# PowerAssembly.net
KiCad netlist of a schematic drawn in Altium Designer
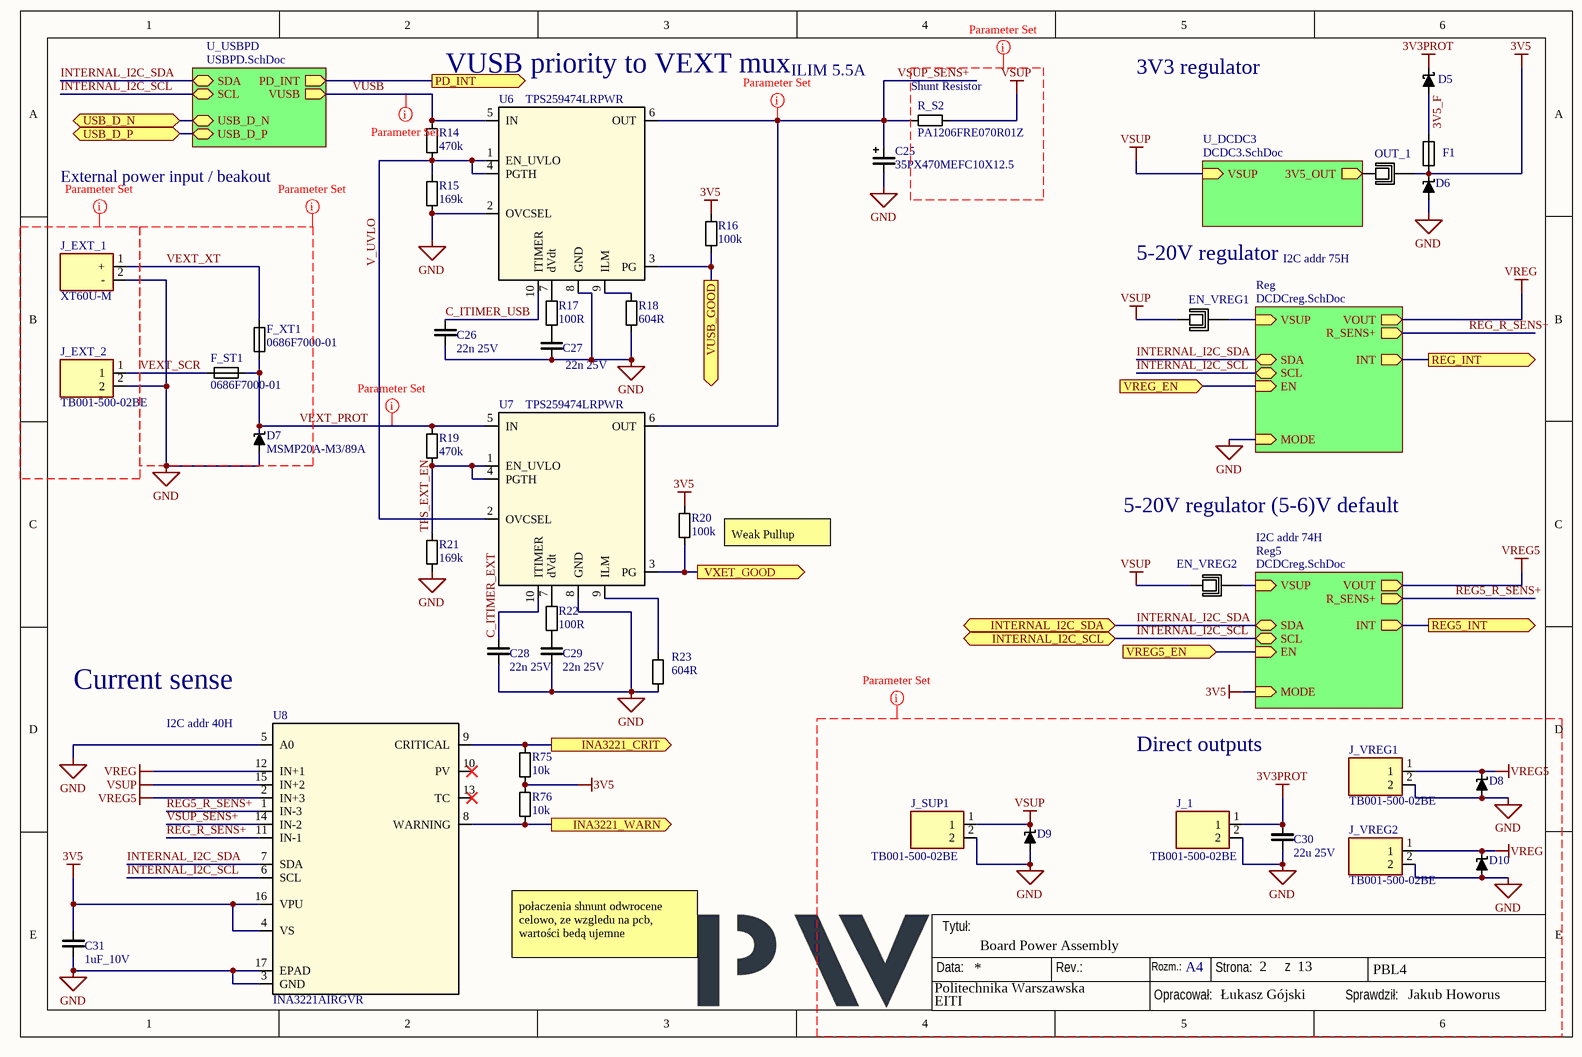
[diagram p0: PowerAssembly.SchDoc]

(export (version "E")
  (design (tool "Eeschema 10.0.6"))
  (components
    (comp (ref "C25")
      (value "35PX470MEFC10X12.5")
      (footprint "CAP_PKPZ_10X12P5_LOW_RUB")
      (description "470 µF 35 V Aluminum Electrolytic Capacitors Radial, Can 2000 Hrs @ 105°C")
      (fields (field (name "VOLTAGE") "35V") (field (name "TOLERANCE") "20%"))
      (libsource (lib "Common") (part "C_Pol_470uF_35V"))
    )
    (comp (ref "C26")
      (value "22n 25V")
      (footprint "C_0603")
      (description "Ceramic capacitor")
      (fields (field (name "VOLTAGE") "25V") (field (name "TOLERANCE") "10%"))
      (libsource (lib "Common") (part "C_22nF_25V"))
    )
    (comp (ref "C27")
      (value "22n 25V")
      (footprint "C_0603")
      (description "Ceramic capacitor")
      (fields (field (name "VOLTAGE") "25V") (field (name "TOLERANCE") "10%"))
      (libsource (lib "Common") (part "C_22nF_25V"))
    )
    (comp (ref "C28")
      (value "22n 25V")
      (footprint "C_0603")
      (description "Ceramic capacitor")
      (fields (field (name "VOLTAGE") "25V") (field (name "TOLERANCE") "10%"))
      (libsource (lib "Common") (part "C_22nF_25V"))
    )
    (comp (ref "C29")
      (value "22n 25V")
      (footprint "C_0603")
      (description "Ceramic capacitor")
      (fields (field (name "VOLTAGE") "25V") (field (name "TOLERANCE") "10%"))
      (libsource (lib "Common") (part "C_22nF_25V"))
    )
    (comp (ref "C30")
      (value "22u 25V")
      (footprint "C_1206")
      (description "Ceramic capacitor")
      (fields (field (name "VOLTAGE") "25V") (field (name "TOLERANCE") "20%"))
      (libsource (lib "Common") (part "C_22uF_25V"))
    )
    (comp (ref "C31")
      (value "1uF_10V")
      (footprint "C_0603")
      (description "Ceramic capacitor")
      (fields (field (name "VOLTAGE") "10V") (field (name "TOLERANCE") "10%"))
      (libsource (lib "Common") (part "C_1uF_10V"))
    )
    (comp (ref "D5")
      (value "SL12-E3/61T")
      (footprint "DIONM5127X229N")
      (description "Schottky Diode 1500mA 30V reverse")
      (libsource (lib "Common") (part "D schottky 1.5A"))
    )
    (comp (ref "D6")
      (value "MSMP20A-M3/89A")
      (footprint "CR_0A-M389A_VIS")
      (description "22V Breakdown MSMP20A-M3/89A")
      (libsource (lib "Common") (part "TVS_22V"))
    )
    (comp (ref "D7")
      (value "MSMP20A-M3/89A")
      (footprint "CR_0A-M389A_VIS")
      (description "22V Breakdown MSMP20A-M3/89A")
      (libsource (lib "Common") (part "TVS_22V"))
    )
    (comp (ref "D8")
      (value "MSMP20A-M3/89A")
      (footprint "CR_0A-M389A_VIS")
      (description "22V Breakdown MSMP20A-M3/89A")
      (libsource (lib "Common") (part "TVS_22V"))
    )
    (comp (ref "D9")
      (value "MSMP20A-M3/89A")
      (footprint "CR_0A-M389A_VIS")
      (description "22V Breakdown MSMP20A-M3/89A")
      (libsource (lib "Common") (part "TVS_22V"))
    )
    (comp (ref "D10")
      (value "MSMP20A-M3/89A")
      (footprint "CR_0A-M389A_VIS")
      (description "22V Breakdown MSMP20A-M3/89A")
      (libsource (lib "Common") (part "TVS_22V"))
    )
    (comp (ref "EN_VREG1")
      (value "JUMPER")
      (footprint "Jumper")
      (description "Jumper on traces")
      (libsource (lib "Common") (part "Jumper x2"))
    )
    (comp (ref "EN_VREG2")
      (value "JUMPER")
      (footprint "Jumper")
      (description "Jumper on traces")
      (libsource (lib "Common") (part "Jumper x2"))
    )
    (comp (ref "F1")
      (value "SD110-08")
      (footprint "1812")
      (description "FUSE PTC 1.1A 8VDC 2.2A TRIP")
      (libsource (lib "PowerLib") (part "PTC 1.1A FUSE"))
    )
    (comp (ref "F_ST1")
      (value "0686F7000-01")
      (footprint "0603_FUSE")
      (description "7A fuse 0603 package")
      (fields (field (name "MANUFACTURER") "Bel fuse Inc."))
      (libsource (lib "PowerLib") (part "F_7A"))
    )
    (comp (ref "F_XT1")
      (value "0686F7000-01")
      (footprint "0603_FUSE")
      (description "7A fuse 0603 package")
      (fields (field (name "MANUFACTURER") "Bel fuse Inc."))
      (libsource (lib "PowerLib") (part "F_7A"))
    )
    (comp (ref "J_1")
      (value "TB001-500-02BE")
      (footprint "TB00150002BE")
      (description "Screw terminal x2 5mm spacing")
      (fields (field (name "MANUFACTURER") "Same Sky"))
      (libsource (lib "Common") (part "Screw Terminal x2 5mm"))
    )
    (comp (ref "J_EXT_1")
      (value "XT60U-M")
      (footprint "XT60U-M")
      (description "XT60 male connector, ewentualnie dostępny w zasobach prywatnych (5szt)")
      (fields (field (name "MANUFACTURER") "AMASS"))
      (libsource (lib "PowerLib") (part "XT60"))
    )
    (comp (ref "J_EXT_2")
      (value "TB001-500-02BE")
      (footprint "TB00150002BE")
      (description "Screw terminal x2 5mm spacing")
      (fields (field (name "MANUFACTURER") "Same Sky"))
      (libsource (lib "Common") (part "Screw Terminal x2 5mm"))
    )
    (comp (ref "J_SUP1")
      (value "TB001-500-02BE")
      (footprint "TB00150002BE")
      (description "Screw terminal x2 5mm spacing")
      (fields (field (name "MANUFACTURER") "Same Sky"))
      (libsource (lib "Common") (part "Screw Terminal x2 5mm"))
    )
    (comp (ref "J_VREG1")
      (value "TB001-500-02BE")
      (footprint "TB00150002BE")
      (description "Screw terminal x2 5mm spacing")
      (fields (field (name "MANUFACTURER") "Same Sky"))
      (libsource (lib "Common") (part "Screw Terminal x2 5mm"))
    )
    (comp (ref "J_VREG2")
      (value "TB001-500-02BE")
      (footprint "TB00150002BE")
      (description "Screw terminal x2 5mm spacing")
      (fields (field (name "MANUFACTURER") "Same Sky"))
      (libsource (lib "Common") (part "Screw Terminal x2 5mm"))
    )
    (comp (ref "OUT_1")
      (value "JUMPER")
      (footprint "Jumper")
      (description "Jumper on traces")
      (libsource (lib "Common") (part "Jumper x2"))
    )
    (comp (ref "R14")
      (value "470k")
      (footprint "R_0603")
      (description "Resistor")
      (fields (field (name "TOLERANCE") "1%") (field (name "POWER") "100mW"))
      (libsource (lib "Common") (part "R_470k"))
    )
    (comp (ref "R15")
      (value "169k")
      (footprint "R_0603")
      (description "Resistor")
      (fields (field (name "TOLERANCE") "1%") (field (name "POWER") "100mW"))
      (libsource (lib "Common") (part "R_169k"))
    )
    (comp (ref "R16")
      (value "100k")
      (footprint "R_0603")
      (description "Resistor")
      (fields (field (name "TOLERANCE") "1%") (field (name "POWER") "100mW"))
      (libsource (lib "Common") (part "R_100k"))
    )
    (comp (ref "R17")
      (value "100R")
      (footprint "R_0603")
      (description "Resistor")
      (fields (field (name "TOLERANCE") "1%") (field (name "POWER") "100mW"))
      (libsource (lib "Common") (part "R_100R"))
    )
    (comp (ref "R18")
      (value "604R")
      (footprint "R_0603")
      (description "Resistor")
      (fields (field (name "TOLERANCE") "1%") (field (name "POWER") "100mW"))
      (libsource (lib "Common") (part "R_604R"))
    )
    (comp (ref "R19")
      (value "470k")
      (footprint "R_0603")
      (description "Resistor")
      (fields (field (name "TOLERANCE") "1%") (field (name "POWER") "100mW"))
      (libsource (lib "Common") (part "R_470k"))
    )
    (comp (ref "R20")
      (value "100k")
      (footprint "R_0603")
      (description "Resistor")
      (fields (field (name "TOLERANCE") "1%") (field (name "POWER") "100mW"))
      (libsource (lib "Common") (part "R_100k"))
    )
    (comp (ref "R21")
      (value "169k")
      (footprint "R_0603")
      (description "Resistor")
      (fields (field (name "TOLERANCE") "1%") (field (name "POWER") "100mW"))
      (libsource (lib "Common") (part "R_169k"))
    )
    (comp (ref "R22")
      (value "100R")
      (footprint "R_0603")
      (description "Resistor")
      (fields (field (name "TOLERANCE") "1%") (field (name "POWER") "100mW"))
      (libsource (lib "Common") (part "R_100R"))
    )
    (comp (ref "R23")
      (value "604R")
      (footprint "R_0603")
      (description "Resistor")
      (fields (field (name "TOLERANCE") "1%") (field (name "POWER") "100mW"))
      (libsource (lib "Common") (part "R_604R"))
    )
    (comp (ref "R75")
      (value "10k")
      (footprint "R_0603")
      (description "Resistor")
      (fields (field (name "TOLERANCE") "1%") (field (name "POWER") "100mW"))
      (libsource (lib "Common") (part "R_10k"))
    )
    (comp (ref "R76")
      (value "10k")
      (footprint "R_0603")
      (description "Resistor")
      (fields (field (name "TOLERANCE") "1%") (field (name "POWER") "100mW"))
      (libsource (lib "Common") (part "R_10k"))
    )
    (comp (ref "R_S2")
      (value "PA1206FRE070R01Z")
      (footprint "R_1206")
      (description "Shunt Resistor 10 mR, 1206, 250mW")
      (fields (field (name "TOLERANCE") "1%") (field (name "POWER") "250mW"))
      (libsource (lib "PowerLib") (part "R_10mR"))
    )
    (comp (ref "U6")
      (value "TPS259474LRPWR")
      (footprint "RPW0010A-MFG")
      (description "2.7-V to 23-V, 5.5-A eFuse with integrated reverse polarity protection 10-VQFN-HR")
      (fields (field (name "MANUFACTURER") "Texas Instruments"))
      (libsource (lib "PowerLib") (part "TPS259474LRPWR"))
    )
    (comp (ref "U7")
      (value "TPS259474LRPWR")
      (footprint "RPW0010A-MFG")
      (description "2.7-V to 23-V, 5.5-A eFuse with integrated reverse polarity protection 10-VQFN-HR")
      (fields (field (name "MANUFACTURER") "Texas Instruments"))
      (libsource (lib "PowerLib") (part "TPS259474LRPWR"))
    )
    (comp (ref "U8")
      (value "INA3221AIRGVR")
      (footprint "RGV16_2P16X2P16")
      (description "26V, triple channel, 13-bit, i2c output current/voltage monitor w/alerts 16-VQFN")
      (fields (field (name "MANUFACTURER") "Texas Instruments"))
      (libsource (lib "PowerLib") (part "INA3221AIRGVR"))
    )
  )
  (nets
    (net (code "1") (name "/3V5_F") (class "Default")
      (node (ref "D5") (pin "A") (pinfunction "A_A") (pintype "passive"))
      (node (ref "F1") (pin "1") (pinfunction "1_1") (pintype "passive"))
    )
    (net (code "2") (name "/3V5_OUT") (class "Default")
      (node (ref "OUT_1") (pin "1") (pinfunction "1_1") (pintype "passive"))
    )
    (net (code "3") (name "/C_ITIMER_EXT") (class "Default")
      (node (ref "C28") (pin "2") (pinfunction "2_2") (pintype "passive"))
      (node (ref "U7") (pin "10") (pinfunction "ITIMER_10") (pintype "passive"))
    )
    (net (code "4") (name "/C_ITIMER_USB") (class "Default")
      (node (ref "C26") (pin "2") (pinfunction "2_2") (pintype "passive"))
      (node (ref "U6") (pin "10") (pinfunction "ITIMER_10") (pintype "passive"))
    )
    (net (code "5") (name "/INA3221_CRIT") (class "Default")
      (node (ref "R75") (pin "2") (pinfunction "2_2") (pintype "passive"))
      (node (ref "U8") (pin "9") (pinfunction "CRITICAL_9") (pintype "passive"))
    )
    (net (code "6") (name "/INA3221_WARN") (class "Default")
      (node (ref "R76") (pin "1") (pinfunction "1_1") (pintype "passive"))
      (node (ref "U8") (pin "8") (pinfunction "WARNING_8") (pintype "passive"))
    )
    (net (code "7") (name "/INTERNAL_I2C_SCL") (class "Default")
      (node (ref "U8") (pin "6") (pinfunction "SCL_6") (pintype "passive"))
    )
    (net (code "8") (name "/INTERNAL_I2C_SDA") (class "Default")
      (node (ref "U8") (pin "7") (pinfunction "SDA_7") (pintype "passive"))
    )
    (net (code "11") (name "/REG5_R_SENS+") (class "Default")
      (node (ref "U8") (pin "1") (pinfunction "IN-3_1") (pintype "passive"))
    )
    (net (code "13") (name "/REG_R_SENS+") (class "Default")
      (node (ref "U8") (pin "11") (pinfunction "IN-1_11") (pintype "passive"))
    )
    (net (code "14") (name "/TPS_EXT_EN") (class "Default")
      (node (ref "R19") (pin "1") (pinfunction "1_1") (pintype "passive"))
      (node (ref "R21") (pin "2") (pinfunction "2_2") (pintype "passive"))
      (node (ref "U7") (pin "1") (pinfunction "EN_UVLO_1") (pintype "passive"))
      (node (ref "U7") (pin "4") (pinfunction "PGTH_4") (pintype "passive"))
    )
    (net (code "17") (name "/VEXT_PROT") (class "Default")
      (node (ref "D7") (pin "K") (pinfunction "K_K") (pintype "passive"))
      (node (ref "F_ST1") (pin "2") (pinfunction "2_2") (pintype "passive"))
      (node (ref "F_XT1") (pin "2") (pinfunction "2_2") (pintype "passive"))
      (node (ref "R19") (pin "2") (pinfunction "2_2") (pintype "passive"))
      (node (ref "U7") (pin "5") (pinfunction "IN_5") (pintype "passive"))
    )
    (net (code "18") (name "/VEXT_SCR") (class "Default")
      (node (ref "F_ST1") (pin "1") (pinfunction "1_1") (pintype "passive"))
      (node (ref "J_EXT_2") (pin "1") (pinfunction "1_1") (pintype "passive"))
    )
    (net (code "19") (name "/VEXT_XT") (class "Default")
      (node (ref "F_XT1") (pin "1") (pinfunction "1_1") (pintype "passive"))
      (node (ref "J_EXT_1") (pin "1") (pinfunction "+_1") (pintype "passive"))
    )
    (net (code "22") (name "/VSUP") (class "Default")
      (node (ref "EN_VREG2") (pin "2") (pinfunction "2_2") (pintype "passive"))
    )
    (net (code "23") (name "/VSUP_1") (class "Default")
      (node (ref "EN_VREG1") (pin "2") (pinfunction "2_2") (pintype "passive"))
    )
    (net (code "24") (name "/VSUP_SENS+") (class "Default")
      (node (ref "C25") (pin "1") (pinfunction "1_1") (pintype "passive"))
      (node (ref "R_S2") (pin "1") (pinfunction "1_1") (pintype "passive"))
      (node (ref "U6") (pin "6") (pinfunction "OUT_6") (pintype "passive"))
      (node (ref "U7") (pin "6") (pinfunction "OUT_6") (pintype "passive"))
      (node (ref "U8") (pin "14") (pinfunction "IN-2_14") (pintype "passive"))
    )
    (net (code "25") (name "/VUSB") (class "Default")
      (node (ref "R14") (pin "2") (pinfunction "2_2") (pintype "passive"))
      (node (ref "U6") (pin "5") (pinfunction "IN_5") (pintype "passive"))
    )
    (net (code "26") (name "/VUSB_GOOD") (class "Default")
      (node (ref "R16") (pin "1") (pinfunction "1_1") (pintype "passive"))
      (node (ref "U6") (pin "3") (pinfunction "PG_3") (pintype "passive"))
    )
    (net (code "27") (name "/V_UVLO") (class "Default")
      (node (ref "R14") (pin "1") (pinfunction "1_1") (pintype "passive"))
      (node (ref "R15") (pin "2") (pinfunction "2_2") (pintype "passive"))
      (node (ref "U6") (pin "1") (pinfunction "EN_UVLO_1") (pintype "passive"))
      (node (ref "U6") (pin "4") (pinfunction "PGTH_4") (pintype "passive"))
      (node (ref "U7") (pin "2") (pinfunction "OVCSEL_2") (pintype "passive"))
    )
    (net (code "28") (name "/VXET_GOOD") (class "Default")
      (node (ref "R20") (pin "1") (pinfunction "1_1") (pintype "passive"))
      (node (ref "U7") (pin "3") (pinfunction "PG_3") (pintype "passive"))
    )
    (net (code "29") (name "3V3PROT") (class "Default")
      (node (ref "C30") (pin "2") (pinfunction "2_2") (pintype "passive"))
      (node (ref "D5") (pin "K") (pinfunction "K_K") (pintype "passive"))
      (node (ref "J_1") (pin "1") (pinfunction "1_1") (pintype "passive"))
    )
    (net (code "30") (name "3V5") (class "Default")
      (node (ref "C31") (pin "2") (pinfunction "2_2") (pintype "passive"))
      (node (ref "D6") (pin "K") (pinfunction "K_K") (pintype "passive"))
      (node (ref "F1") (pin "2") (pinfunction "2_2") (pintype "passive"))
      (node (ref "OUT_1") (pin "2") (pinfunction "2_2") (pintype "passive"))
      (node (ref "R16") (pin "2") (pinfunction "2_2") (pintype "passive"))
      (node (ref "R20") (pin "2") (pinfunction "2_2") (pintype "passive"))
      (node (ref "R75") (pin "1") (pinfunction "1_1") (pintype "passive"))
      (node (ref "R76") (pin "2") (pinfunction "2_2") (pintype "passive"))
      (node (ref "U8") (pin "16") (pinfunction "VPU_16") (pintype "passive"))
      (node (ref "U8") (pin "4") (pinfunction "VS_4") (pintype "passive"))
    )
    (net (code "31") (name "GND") (class "Default")
      (node (ref "C25") (pin "2") (pinfunction "2_2") (pintype "passive"))
      (node (ref "C26") (pin "1") (pinfunction "1_1") (pintype "passive"))
      (node (ref "C27") (pin "1") (pinfunction "1_1") (pintype "passive"))
      (node (ref "C28") (pin "1") (pinfunction "1_1") (pintype "passive"))
      (node (ref "C29") (pin "1") (pinfunction "1_1") (pintype "passive"))
      (node (ref "C30") (pin "1") (pinfunction "1_1") (pintype "passive"))
      (node (ref "C31") (pin "1") (pinfunction "1_1") (pintype "passive"))
      (node (ref "D10") (pin "A") (pinfunction "A_A") (pintype "passive"))
      (node (ref "D6") (pin "A") (pinfunction "A_A") (pintype "passive"))
      (node (ref "D7") (pin "A") (pinfunction "A_A") (pintype "passive"))
      (node (ref "D8") (pin "A") (pinfunction "A_A") (pintype "passive"))
      (node (ref "D9") (pin "A") (pinfunction "A_A") (pintype "passive"))
      (node (ref "J_1") (pin "2") (pinfunction "2_2") (pintype "passive"))
      (node (ref "J_EXT_1") (pin "2") (pinfunction "-_2") (pintype "passive"))
      (node (ref "J_EXT_2") (pin "2") (pinfunction "2_2") (pintype "passive"))
      (node (ref "J_SUP1") (pin "2") (pinfunction "2_2") (pintype "passive"))
      (node (ref "J_VREG1") (pin "2") (pinfunction "2_2") (pintype "passive"))
      (node (ref "J_VREG2") (pin "2") (pinfunction "2_2") (pintype "passive"))
      (node (ref "R15") (pin "1") (pinfunction "1_1") (pintype "passive"))
      (node (ref "R18") (pin "1") (pinfunction "1_1") (pintype "passive"))
      (node (ref "R21") (pin "1") (pinfunction "1_1") (pintype "passive"))
      (node (ref "R23") (pin "1") (pinfunction "1_1") (pintype "passive"))
      (node (ref "U6") (pin "2") (pinfunction "OVCSEL_2") (pintype "passive"))
      (node (ref "U6") (pin "8") (pinfunction "GND_8") (pintype "passive"))
      (node (ref "U7") (pin "8") (pinfunction "GND_8") (pintype "passive"))
      (node (ref "U8") (pin "17") (pinfunction "EPAD_17") (pintype "passive"))
      (node (ref "U8") (pin "3") (pinfunction "GND_3") (pintype "passive"))
      (node (ref "U8") (pin "5") (pinfunction "A0_5") (pintype "passive"))
    )
    (net (code "32") (name "Net-(C27-Pad2)") (class "Default")
      (node (ref "C27") (pin "2") (pinfunction "2_2") (pintype "passive"))
      (node (ref "R17") (pin "1") (pinfunction "1_1") (pintype "passive"))
    )
    (net (code "33") (name "Net-(C29-Pad2)") (class "Default")
      (node (ref "C29") (pin "2") (pinfunction "2_2") (pintype "passive"))
      (node (ref "R22") (pin "1") (pinfunction "1_1") (pintype "passive"))
    )
    (net (code "34") (name "Net-(U6-ILM)") (class "Default")
      (node (ref "R18") (pin "2") (pinfunction "2_2") (pintype "passive"))
      (node (ref "U6") (pin "9") (pinfunction "ILM_9") (pintype "passive"))
    )
    (net (code "35") (name "Net-(U6-dVdt)") (class "Default")
      (node (ref "R17") (pin "2") (pinfunction "2_2") (pintype "passive"))
      (node (ref "U6") (pin "7") (pinfunction "dVdt_7") (pintype "passive"))
    )
    (net (code "36") (name "Net-(U7-ILM)") (class "Default")
      (node (ref "R23") (pin "2") (pinfunction "2_2") (pintype "passive"))
      (node (ref "U7") (pin "9") (pinfunction "ILM_9") (pintype "passive"))
    )
    (net (code "37") (name "Net-(U7-dVdt)") (class "Default")
      (node (ref "R22") (pin "2") (pinfunction "2_2") (pintype "passive"))
      (node (ref "U7") (pin "7") (pinfunction "dVdt_7") (pintype "passive"))
    )
    (net (code "38") (name "VREG") (class "Default")
      (node (ref "D10") (pin "K") (pinfunction "K_K") (pintype "passive"))
      (node (ref "J_VREG2") (pin "1") (pinfunction "1_1") (pintype "passive"))
      (node (ref "U8") (pin "12") (pinfunction "IN+1_12") (pintype "passive"))
    )
    (net (code "39") (name "VREG5") (class "Default")
      (node (ref "D8") (pin "K") (pinfunction "K_K") (pintype "passive"))
      (node (ref "J_VREG1") (pin "1") (pinfunction "1_1") (pintype "passive"))
      (node (ref "U8") (pin "2") (pinfunction "IN+3_2") (pintype "passive"))
    )
    (net (code "40") (name "VSUP") (class "Default")
      (node (ref "D9") (pin "K") (pinfunction "K_K") (pintype "passive"))
      (node (ref "EN_VREG1") (pin "1") (pinfunction "1_1") (pintype "passive"))
      (node (ref "EN_VREG2") (pin "1") (pinfunction "1_1") (pintype "passive"))
      (node (ref "J_SUP1") (pin "1") (pinfunction "1_1") (pintype "passive"))
      (node (ref "R_S2") (pin "2") (pinfunction "2_2") (pintype "passive"))
      (node (ref "U8") (pin "15") (pinfunction "IN+2_15") (pintype "passive"))
    )
    (net (code "41") (name "unconnected-(U8-PV-Pad10)") (class "Default")
      (node (ref "U8") (pin "10") (pinfunction "PV_10") (pintype "passive+no_connect"))
    )
    (net (code "42") (name "unconnected-(U8-TC-Pad13)") (class "Default")
      (node (ref "U8") (pin "13") (pinfunction "TC_13") (pintype "passive+no_connect"))
    )
  )
)
